# DSP_Power_Analog.net
KiCad netlist of a schematic drawn in Altium Designer
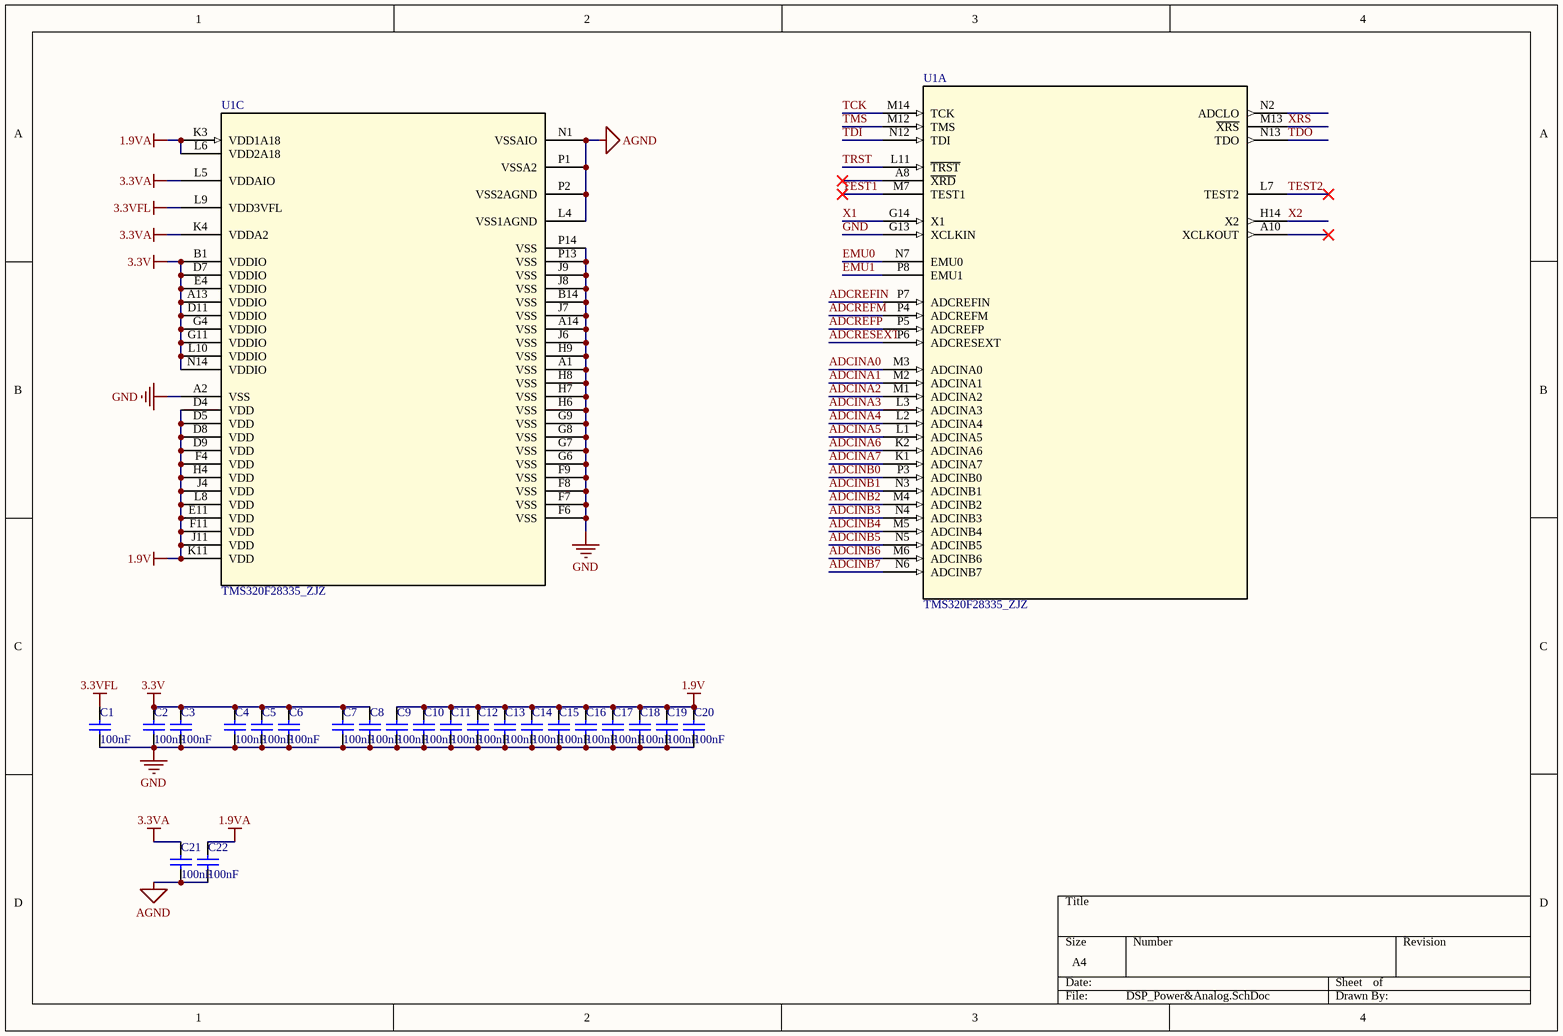
[diagram p0: DSP_Power&Analog.SchDoc]

(export (version "E")
  (design (tool "Eeschema 10.0.6"))
  (components
    (comp (ref "C1")
      (value "100nF")
      (footprint "C0402")
      (description "Capacitor")
      (fields (field (name "Comment") "Cap") (field (name "PUBLISHER") "Altium Limited"))
      (libsource (lib "Miscellaneous Devices") (part "Cap"))
    )
    (comp (ref "C2")
      (value "100nF")
      (footprint "C0402")
      (description "Capacitor")
      (fields (field (name "Comment") "Cap") (field (name "PUBLISHER") "Altium Limited"))
      (libsource (lib "Miscellaneous Devices") (part "Cap"))
    )
    (comp (ref "C3")
      (value "100nF")
      (footprint "C0402")
      (description "Capacitor")
      (fields (field (name "Comment") "Cap") (field (name "PUBLISHER") "Altium Limited"))
      (libsource (lib "Miscellaneous Devices") (part "Cap"))
    )
    (comp (ref "C4")
      (value "100nF")
      (footprint "C0402")
      (description "Capacitor")
      (fields (field (name "Comment") "Cap") (field (name "PUBLISHER") "Altium Limited"))
      (libsource (lib "Miscellaneous Devices") (part "Cap"))
    )
    (comp (ref "C5")
      (value "100nF")
      (footprint "C0402")
      (description "Capacitor")
      (fields (field (name "Comment") "Cap") (field (name "PUBLISHER") "Altium Limited"))
      (libsource (lib "Miscellaneous Devices") (part "Cap"))
    )
    (comp (ref "C6")
      (value "100nF")
      (footprint "C0402")
      (description "Capacitor")
      (fields (field (name "Comment") "Cap") (field (name "PUBLISHER") "Altium Limited"))
      (libsource (lib "Miscellaneous Devices") (part "Cap"))
    )
    (comp (ref "C7")
      (value "100nF")
      (footprint "C0603")
      (description "Capacitor")
      (fields (field (name "Comment") "Cap") (field (name "PUBLISHER") "Altium Limited"))
      (libsource (lib "Miscellaneous Devices") (part "Cap"))
    )
    (comp (ref "C8")
      (value "100nF")
      (footprint "C0603")
      (description "Capacitor")
      (fields (field (name "Comment") "Cap") (field (name "PUBLISHER") "Altium Limited"))
      (libsource (lib "Miscellaneous Devices") (part "Cap"))
    )
    (comp (ref "C9")
      (value "100nF")
      (footprint "C0402")
      (description "Capacitor")
      (fields (field (name "Comment") "Cap") (field (name "PUBLISHER") "Altium Limited"))
      (libsource (lib "Miscellaneous Devices") (part "Cap"))
    )
    (comp (ref "C10")
      (value "100nF")
      (footprint "C0402")
      (description "Capacitor")
      (fields (field (name "Comment") "Cap") (field (name "PUBLISHER") "Altium Limited"))
      (libsource (lib "Miscellaneous Devices") (part "Cap"))
    )
    (comp (ref "C11")
      (value "100nF")
      (footprint "C0402")
      (description "Capacitor")
      (fields (field (name "Comment") "Cap") (field (name "PUBLISHER") "Altium Limited"))
      (libsource (lib "Miscellaneous Devices") (part "Cap"))
    )
    (comp (ref "C12")
      (value "100nF")
      (footprint "C0402")
      (description "Capacitor")
      (fields (field (name "Comment") "Cap") (field (name "PUBLISHER") "Altium Limited"))
      (libsource (lib "Miscellaneous Devices") (part "Cap"))
    )
    (comp (ref "C13")
      (value "100nF")
      (footprint "C0402")
      (description "Capacitor")
      (fields (field (name "Comment") "Cap") (field (name "PUBLISHER") "Altium Limited"))
      (libsource (lib "Miscellaneous Devices") (part "Cap"))
    )
    (comp (ref "C14")
      (value "100nF")
      (footprint "C0402")
      (description "Capacitor")
      (fields (field (name "Comment") "Cap") (field (name "PUBLISHER") "Altium Limited"))
      (libsource (lib "Miscellaneous Devices") (part "Cap"))
    )
    (comp (ref "C15")
      (value "100nF")
      (footprint "C0402")
      (description "Capacitor")
      (fields (field (name "Comment") "Cap") (field (name "PUBLISHER") "Altium Limited"))
      (libsource (lib "Miscellaneous Devices") (part "Cap"))
    )
    (comp (ref "C16")
      (value "100nF")
      (footprint "C0402")
      (description "Capacitor")
      (fields (field (name "Comment") "Cap") (field (name "PUBLISHER") "Altium Limited"))
      (libsource (lib "Miscellaneous Devices") (part "Cap"))
    )
    (comp (ref "C17")
      (value "100nF")
      (footprint "C0402")
      (description "Capacitor")
      (fields (field (name "Comment") "Cap") (field (name "PUBLISHER") "Altium Limited"))
      (libsource (lib "Miscellaneous Devices") (part "Cap"))
    )
    (comp (ref "C18")
      (value "100nF")
      (footprint "C0402")
      (description "Capacitor")
      (fields (field (name "Comment") "Cap") (field (name "PUBLISHER") "Altium Limited"))
      (libsource (lib "Miscellaneous Devices") (part "Cap"))
    )
    (comp (ref "C19")
      (value "100nF")
      (footprint "C0402")
      (description "Capacitor")
      (fields (field (name "Comment") "Cap") (field (name "PUBLISHER") "Altium Limited"))
      (libsource (lib "Miscellaneous Devices") (part "Cap"))
    )
    (comp (ref "C20")
      (value "100nF")
      (footprint "C0402")
      (description "Capacitor")
      (fields (field (name "Comment") "Cap") (field (name "PUBLISHER") "Altium Limited"))
      (libsource (lib "Miscellaneous Devices") (part "Cap"))
    )
    (comp (ref "C21")
      (value "100nF")
      (footprint "C0402")
      (description "Capacitor")
      (fields (field (name "Comment") "Cap") (field (name "PUBLISHER") "Altium Limited"))
      (libsource (lib "Miscellaneous Devices") (part "Cap"))
    )
    (comp (ref "C22")
      (value "100nF")
      (footprint "C0402")
      (description "Capacitor")
      (fields (field (name "Comment") "Cap") (field (name "PUBLISHER") "Altium Limited"))
      (libsource (lib "Miscellaneous Devices") (part "Cap"))
    )
    (comp (ref "U1")
      (value "TMS320F28335_ZJZ")
      (footprint "ZJZ176")
      (description "Imported")
      (fields
        (field (name "MANUFACTURER") "Texas Instruments")
        (field (name "GENERIC_PART_NUMBER") "TMS320F28335")
      )
      (libsource (lib "schlib_by_wjy") (part "TMS320F28335_ZJZ"))
    )
  )
  (nets
    (net (code "1") (name "/ADCINA0") (class "Default")
      (node (ref "U1") (pin "M3") (pinfunction "ADCINA0_M3") (pintype "input"))
    )
    (net (code "2") (name "/ADCINA1") (class "Default")
      (node (ref "U1") (pin "M2") (pinfunction "ADCINA1_M2") (pintype "input"))
    )
    (net (code "3") (name "/ADCINA2") (class "Default")
      (node (ref "U1") (pin "M1") (pinfunction "ADCINA2_M1") (pintype "input"))
    )
    (net (code "4") (name "/ADCINA3") (class "Default")
      (node (ref "U1") (pin "L3") (pinfunction "ADCINA3_L3") (pintype "input"))
    )
    (net (code "5") (name "/ADCINA4") (class "Default")
      (node (ref "U1") (pin "L2") (pinfunction "ADCINA4_L2") (pintype "input"))
    )
    (net (code "6") (name "/ADCINA5") (class "Default")
      (node (ref "U1") (pin "L1") (pinfunction "ADCINA5_L1") (pintype "input"))
    )
    (net (code "7") (name "/ADCINA6") (class "Default")
      (node (ref "U1") (pin "K2") (pinfunction "ADCINA6_K2") (pintype "input"))
    )
    (net (code "8") (name "/ADCINA7") (class "Default")
      (node (ref "U1") (pin "K1") (pinfunction "ADCINA7_K1") (pintype "input"))
    )
    (net (code "9") (name "/ADCINB0") (class "Default")
      (node (ref "U1") (pin "P3") (pinfunction "ADCINB0_P3") (pintype "input"))
    )
    (net (code "10") (name "/ADCINB1") (class "Default")
      (node (ref "U1") (pin "N3") (pinfunction "ADCINB1_N3") (pintype "input"))
    )
    (net (code "11") (name "/ADCINB2") (class "Default")
      (node (ref "U1") (pin "M4") (pinfunction "ADCINB2_M4") (pintype "input"))
    )
    (net (code "12") (name "/ADCINB3") (class "Default")
      (node (ref "U1") (pin "N4") (pinfunction "ADCINB3_N4") (pintype "input"))
    )
    (net (code "13") (name "/ADCINB4") (class "Default")
      (node (ref "U1") (pin "M5") (pinfunction "ADCINB4_M5") (pintype "input"))
    )
    (net (code "14") (name "/ADCINB5") (class "Default")
      (node (ref "U1") (pin "N5") (pinfunction "ADCINB5_N5") (pintype "input"))
    )
    (net (code "15") (name "/ADCINB6") (class "Default")
      (node (ref "U1") (pin "M6") (pinfunction "ADCINB6_M6") (pintype "input"))
    )
    (net (code "16") (name "/ADCINB7") (class "Default")
      (node (ref "U1") (pin "N6") (pinfunction "ADCINB7_N6") (pintype "input"))
    )
    (net (code "17") (name "/ADCREFIN") (class "Default")
      (node (ref "U1") (pin "P7") (pinfunction "ADCREFIN_P7") (pintype "input"))
    )
    (net (code "18") (name "/ADCREFM") (class "Default")
      (node (ref "U1") (pin "P4") (pinfunction "ADCREFM_P4") (pintype "input"))
    )
    (net (code "19") (name "/ADCREFP") (class "Default")
      (node (ref "U1") (pin "P5") (pinfunction "ADCREFP_P5") (pintype "input"))
    )
    (net (code "20") (name "/ADCRESEXT") (class "Default")
      (node (ref "U1") (pin "P6") (pinfunction "ADCRESEXT_P6") (pintype "input"))
    )
    (net (code "21") (name "/EMU0") (class "Default")
      (node (ref "U1") (pin "N7") (pinfunction "EMU0_N7") (pintype "passive"))
    )
    (net (code "22") (name "/EMU1") (class "Default")
      (node (ref "U1") (pin "P8") (pinfunction "EMU1_P8") (pintype "passive"))
    )
    (net (code "23") (name "/TCK") (class "Default")
      (node (ref "U1") (pin "M14") (pinfunction "TCK_M14") (pintype "input"))
    )
    (net (code "24") (name "/TDI") (class "Default")
      (node (ref "U1") (pin "N12") (pinfunction "TDI_N12") (pintype "input"))
    )
    (net (code "25") (name "/TDO") (class "Default")
      (node (ref "U1") (pin "N13") (pinfunction "TDO_N13") (pintype "output"))
    )
    (net (code "26") (name "/TEST1") (class "Default")
      (node (ref "U1") (pin "M7") (pinfunction "TEST1_M7") (pintype "passive+no_connect"))
    )
    (net (code "27") (name "/TEST2") (class "Default")
      (node (ref "U1") (pin "L7") (pinfunction "TEST2_L7") (pintype "passive+no_connect"))
    )
    (net (code "28") (name "/TMS") (class "Default")
      (node (ref "U1") (pin "M12") (pinfunction "TMS_M12") (pintype "input"))
    )
    (net (code "29") (name "/TRST") (class "Default")
      (node (ref "U1") (pin "L11") (pinfunction "~{TRST}_L11") (pintype "input"))
    )
    (net (code "30") (name "/X1") (class "Default")
      (node (ref "U1") (pin "G14") (pinfunction "X1_G14") (pintype "input"))
    )
    (net (code "31") (name "/X2") (class "Default")
      (node (ref "U1") (pin "H14") (pinfunction "X2_H14") (pintype "output"))
    )
    (net (code "32") (name "/XRS") (class "Default")
      (node (ref "U1") (pin "M13") (pinfunction "~{XRS}_M13") (pintype "passive"))
    )
    (net (code "33") (name "1.9V") (class "Default")
      (node (ref "C10") (pin "1") (pinfunction "1_1") (pintype "passive"))
      (node (ref "C11") (pin "1") (pinfunction "1_1") (pintype "passive"))
      (node (ref "C12") (pin "1") (pinfunction "1_1") (pintype "passive"))
      (node (ref "C13") (pin "1") (pinfunction "1_1") (pintype "passive"))
      (node (ref "C14") (pin "1") (pinfunction "1_1") (pintype "passive"))
      (node (ref "C15") (pin "1") (pinfunction "1_1") (pintype "passive"))
      (node (ref "C16") (pin "1") (pinfunction "1_1") (pintype "passive"))
      (node (ref "C17") (pin "1") (pinfunction "1_1") (pintype "passive"))
      (node (ref "C18") (pin "1") (pinfunction "1_1") (pintype "passive"))
      (node (ref "C19") (pin "1") (pinfunction "1_1") (pintype "passive"))
      (node (ref "C20") (pin "1") (pinfunction "1_1") (pintype "passive"))
      (node (ref "C9") (pin "1") (pinfunction "1_1") (pintype "passive"))
      (node (ref "U1") (pin "D4") (pinfunction "VDD_D4") (pintype "power_in"))
      (node (ref "U1") (pin "D5") (pinfunction "VDD_D5") (pintype "power_in"))
      (node (ref "U1") (pin "D8") (pinfunction "VDD_D8") (pintype "power_in"))
      (node (ref "U1") (pin "D9") (pinfunction "VDD_D9") (pintype "power_in"))
      (node (ref "U1") (pin "E11") (pinfunction "VDD_E11") (pintype "power_in"))
      (node (ref "U1") (pin "F11") (pinfunction "VDD_F11") (pintype "power_in"))
      (node (ref "U1") (pin "F4") (pinfunction "VDD_F4") (pintype "power_in"))
      (node (ref "U1") (pin "H4") (pinfunction "VDD_H4") (pintype "power_in"))
      (node (ref "U1") (pin "J11") (pinfunction "VDD_J11") (pintype "power_in"))
      (node (ref "U1") (pin "J4") (pinfunction "VDD_J4") (pintype "power_in"))
      (node (ref "U1") (pin "K11") (pinfunction "VDD_K11") (pintype "power_in"))
      (node (ref "U1") (pin "L8") (pinfunction "VDD_L8") (pintype "power_in"))
    )
    (net (code "34") (name "1.9VA") (class "Default")
      (node (ref "C22") (pin "1") (pinfunction "1_1") (pintype "passive"))
      (node (ref "U1") (pin "K3") (pinfunction "VDD1A18_K3") (pintype "input"))
      (node (ref "U1") (pin "L6") (pinfunction "VDD2A18_L6") (pintype "power_in"))
    )
    (net (code "35") (name "3.3V") (class "Default")
      (node (ref "C2") (pin "1") (pinfunction "1_1") (pintype "passive"))
      (node (ref "C3") (pin "1") (pinfunction "1_1") (pintype "passive"))
      (node (ref "C4") (pin "1") (pinfunction "1_1") (pintype "passive"))
      (node (ref "C5") (pin "1") (pinfunction "1_1") (pintype "passive"))
      (node (ref "C6") (pin "1") (pinfunction "1_1") (pintype "passive"))
      (node (ref "C7") (pin "1") (pinfunction "1_1") (pintype "passive"))
      (node (ref "C8") (pin "1") (pinfunction "1_1") (pintype "passive"))
      (node (ref "U1") (pin "A13") (pinfunction "VDDIO_A13") (pintype "power_in"))
      (node (ref "U1") (pin "B1") (pinfunction "VDDIO_B1") (pintype "power_in"))
      (node (ref "U1") (pin "D11") (pinfunction "VDDIO_D11") (pintype "power_in"))
      (node (ref "U1") (pin "D7") (pinfunction "VDDIO_D7") (pintype "power_in"))
      (node (ref "U1") (pin "E4") (pinfunction "VDDIO_E4") (pintype "power_in"))
      (node (ref "U1") (pin "G11") (pinfunction "VDDIO_G11") (pintype "power_in"))
      (node (ref "U1") (pin "G4") (pinfunction "VDDIO_G4") (pintype "power_in"))
      (node (ref "U1") (pin "L10") (pinfunction "VDDIO_L10") (pintype "power_in"))
      (node (ref "U1") (pin "N14") (pinfunction "VDDIO_N14") (pintype "power_in"))
    )
    (net (code "36") (name "3.3VA") (class "Default")
      (node (ref "C21") (pin "1") (pinfunction "1_1") (pintype "passive"))
      (node (ref "U1") (pin "K4") (pinfunction "VDDA2_K4") (pintype "power_in"))
      (node (ref "U1") (pin "L5") (pinfunction "VDDAIO_L5") (pintype "power_in"))
    )
    (net (code "37") (name "3.3VFL") (class "Default")
      (node (ref "C1") (pin "1") (pinfunction "1_1") (pintype "passive"))
      (node (ref "U1") (pin "L9") (pinfunction "VDD3VFL_L9") (pintype "power_in"))
    )
    (net (code "38") (name "AGND") (class "Default")
      (node (ref "C21") (pin "2") (pinfunction "2_2") (pintype "passive"))
      (node (ref "C22") (pin "2") (pinfunction "2_2") (pintype "passive"))
      (node (ref "U1") (pin "L4") (pinfunction "VSS1AGND_L4") (pintype "power_in"))
      (node (ref "U1") (pin "N1") (pinfunction "VSSAIO_N1") (pintype "power_in"))
      (node (ref "U1") (pin "P1") (pinfunction "VSSA2_P1") (pintype "power_in"))
      (node (ref "U1") (pin "P2") (pinfunction "VSS2AGND_P2") (pintype "power_in"))
    )
    (net (code "39") (name "GND") (class "Default")
      (node (ref "C1") (pin "2") (pinfunction "2_2") (pintype "passive"))
      (node (ref "C10") (pin "2") (pinfunction "2_2") (pintype "passive"))
      (node (ref "C11") (pin "2") (pinfunction "2_2") (pintype "passive"))
      (node (ref "C12") (pin "2") (pinfunction "2_2") (pintype "passive"))
      (node (ref "C13") (pin "2") (pinfunction "2_2") (pintype "passive"))
      (node (ref "C14") (pin "2") (pinfunction "2_2") (pintype "passive"))
      (node (ref "C15") (pin "2") (pinfunction "2_2") (pintype "passive"))
      (node (ref "C16") (pin "2") (pinfunction "2_2") (pintype "passive"))
      (node (ref "C17") (pin "2") (pinfunction "2_2") (pintype "passive"))
      (node (ref "C18") (pin "2") (pinfunction "2_2") (pintype "passive"))
      (node (ref "C19") (pin "2") (pinfunction "2_2") (pintype "passive"))
      (node (ref "C2") (pin "2") (pinfunction "2_2") (pintype "passive"))
      (node (ref "C20") (pin "2") (pinfunction "2_2") (pintype "passive"))
      (node (ref "C3") (pin "2") (pinfunction "2_2") (pintype "passive"))
      (node (ref "C4") (pin "2") (pinfunction "2_2") (pintype "passive"))
      (node (ref "C5") (pin "2") (pinfunction "2_2") (pintype "passive"))
      (node (ref "C6") (pin "2") (pinfunction "2_2") (pintype "passive"))
      (node (ref "C7") (pin "2") (pinfunction "2_2") (pintype "passive"))
      (node (ref "C8") (pin "2") (pinfunction "2_2") (pintype "passive"))
      (node (ref "C9") (pin "2") (pinfunction "2_2") (pintype "passive"))
      (node (ref "U1") (pin "A1") (pinfunction "VSS_A1") (pintype "power_in"))
      (node (ref "U1") (pin "A14") (pinfunction "VSS_A14") (pintype "power_in"))
      (node (ref "U1") (pin "A2") (pinfunction "VSS_A2") (pintype "power_in"))
      (node (ref "U1") (pin "B14") (pinfunction "VSS_B14") (pintype "power_in"))
      (node (ref "U1") (pin "F6") (pinfunction "VSS_F6") (pintype "power_in"))
      (node (ref "U1") (pin "F7") (pinfunction "VSS_F7") (pintype "power_in"))
      (node (ref "U1") (pin "F8") (pinfunction "VSS_F8") (pintype "power_in"))
      (node (ref "U1") (pin "F9") (pinfunction "VSS_F9") (pintype "power_in"))
      (node (ref "U1") (pin "G13") (pinfunction "XCLKIN_G13") (pintype "input"))
      (node (ref "U1") (pin "G6") (pinfunction "VSS_G6") (pintype "power_in"))
      (node (ref "U1") (pin "G7") (pinfunction "VSS_G7") (pintype "power_in"))
      (node (ref "U1") (pin "G8") (pinfunction "VSS_G8") (pintype "power_in"))
      (node (ref "U1") (pin "G9") (pinfunction "VSS_G9") (pintype "power_in"))
      (node (ref "U1") (pin "H6") (pinfunction "VSS_H6") (pintype "power_in"))
      (node (ref "U1") (pin "H7") (pinfunction "VSS_H7") (pintype "power_in"))
      (node (ref "U1") (pin "H8") (pinfunction "VSS_H8") (pintype "power_in"))
      (node (ref "U1") (pin "H9") (pinfunction "VSS_H9") (pintype "power_in"))
      (node (ref "U1") (pin "J6") (pinfunction "VSS_J6") (pintype "power_in"))
      (node (ref "U1") (pin "J7") (pinfunction "VSS_J7") (pintype "power_in"))
      (node (ref "U1") (pin "J8") (pinfunction "VSS_J8") (pintype "power_in"))
      (node (ref "U1") (pin "J9") (pinfunction "VSS_J9") (pintype "power_in"))
      (node (ref "U1") (pin "P13") (pinfunction "VSS_P13") (pintype "power_in"))
      (node (ref "U1") (pin "P14") (pinfunction "VSS_P14") (pintype "power_in"))
    )
    (net (code "40") (name "unconnected-(U1A-ADCLO-PadN2)") (class "Default")
      (node (ref "U1") (pin "N2") (pinfunction "ADCLO_N2") (pintype "output"))
    )
    (net (code "41") (name "unconnected-(U1A-XCLKOUT-PadA10)") (class "Default")
      (node (ref "U1") (pin "A10") (pinfunction "XCLKOUT_A10") (pintype "output+no_connect"))
    )
    (net (code "42") (name "unconnected-(U1A-~{XRD}-PadA8)") (class "Default")
      (node (ref "U1") (pin "A8") (pinfunction "~{XRD}_A8") (pintype "passive+no_connect"))
    )
  )
)
